# pcb_transformer_test.net
KiCad netlist of a schematic drawn in EAGLE
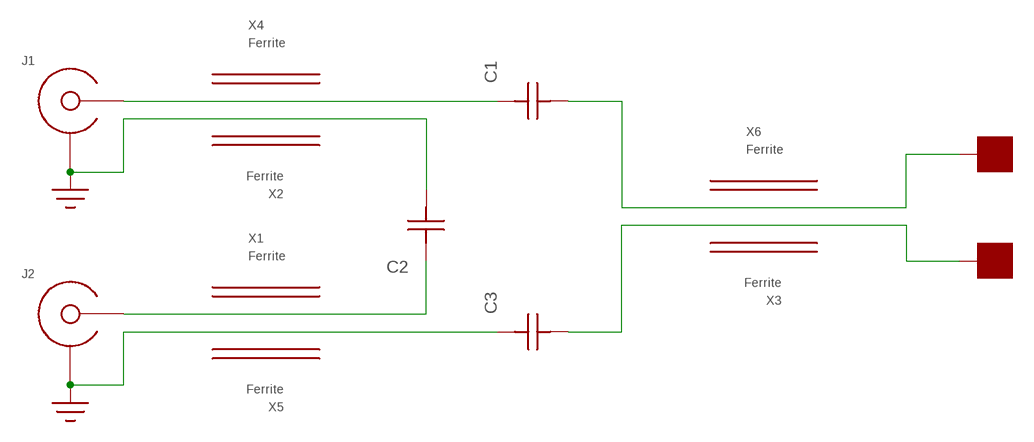
[diagram p0: schematic, sheet 1]

(export (version "E")
  (design (tool "Eeschema 10.0.6"))
  (components
    (comp (ref "C1")
      (value "C0603")
      (footprint "eagle-import:C0603")
      (libsource (lib "eagle-import") (part "C0603"))
    )
    (comp (ref "C2")
      (value "C0603")
      (footprint "eagle-import:C0603")
      (libsource (lib "eagle-import") (part "C0603"))
    )
    (comp (ref "C3")
      (value "C0603")
      (footprint "eagle-import:C0603")
      (libsource (lib "eagle-import") (part "C0603"))
    )
    (comp (ref "J1")
      (value "EDGE_LAUNCH_JACK")
      (footprint "eagle-import:EDGE_LAUNCH_RF_CON")
      (libsource (lib "eagle-import") (part "EDGE_LAUNCH_JACK"))
    )
    (comp (ref "J2")
      (value "EDGE_LAUNCH_JACK")
      (footprint "eagle-import:EDGE_LAUNCH_RF_CON")
      (libsource (lib "eagle-import") (part "EDGE_LAUNCH_JACK"))
    )
    (comp (ref "U$2")
      (value "PAD50MIL")
      (footprint "eagle-import:PAD_50MIL")
      (libsource (lib "eagle-import") (part "PAD50MIL"))
    )
    (comp (ref "U$5")
      (value "PAD50MIL")
      (footprint "eagle-import:PAD_50MIL")
      (libsource (lib "eagle-import") (part "PAD50MIL"))
    )
    (comp (ref "X1")
      (value "Ferrite")
      (footprint "eagle-import:FERRITE-MP0350")
      (libsource (lib "eagle-import") (part "FERRITE_PLATE"))
    )
    (comp (ref "X2")
      (value "Ferrite")
      (footprint "eagle-import:FERRITE-MP0350")
      (libsource (lib "eagle-import") (part "FERRITE_PLATE"))
    )
    (comp (ref "X3")
      (value "Ferrite")
      (footprint "eagle-import:FERRITE-MP0350")
      (libsource (lib "eagle-import") (part "FERRITE_PLATE"))
    )
    (comp (ref "X4")
      (value "Ferrite")
      (footprint "eagle-import:FERRITE-MP0350")
      (libsource (lib "eagle-import") (part "FERRITE_PLATE"))
    )
    (comp (ref "X5")
      (value "Ferrite")
      (footprint "eagle-import:FERRITE-MP0350")
      (libsource (lib "eagle-import") (part "FERRITE_PLATE"))
    )
    (comp (ref "X6")
      (value "Ferrite")
      (footprint "eagle-import:FERRITE-MP0350")
      (libsource (lib "eagle-import") (part "FERRITE_PLATE"))
    )
  )
  (nets
    (net (code "1") (name "GND") (class "Default")
      (node (ref "C2") (pin "P$1") (pinfunction "P$1_P$1") (pintype "bidirectional"))
      (node (ref "C3") (pin "P$2") (pinfunction "P$2_P$2") (pintype "bidirectional"))
      (node (ref "J1") (pin "GND@1") (pinfunction "SHIELD_GND@1") (pintype "bidirectional"))
      (node (ref "J1") (pin "GND@10") (pinfunction "SHIELD_GND@10") (pintype "bidirectional"))
      (node (ref "J1") (pin "GND@11") (pinfunction "SHIELD_GND@11") (pintype "bidirectional"))
      (node (ref "J1") (pin "GND@12") (pinfunction "SHIELD_GND@12") (pintype "bidirectional"))
      (node (ref "J1") (pin "GND@2") (pinfunction "SHIELD_GND@2") (pintype "bidirectional"))
      (node (ref "J1") (pin "GND@3") (pinfunction "SHIELD_GND@3") (pintype "bidirectional"))
      (node (ref "J1") (pin "GND@4") (pinfunction "SHIELD_GND@4") (pintype "bidirectional"))
      (node (ref "J1") (pin "GND@5") (pinfunction "SHIELD_GND@5") (pintype "bidirectional"))
      (node (ref "J1") (pin "GND@6") (pinfunction "SHIELD_GND@6") (pintype "bidirectional"))
      (node (ref "J1") (pin "GND@7") (pinfunction "SHIELD_GND@7") (pintype "bidirectional"))
      (node (ref "J1") (pin "GND@8") (pinfunction "SHIELD_GND@8") (pintype "bidirectional"))
      (node (ref "J1") (pin "GND@9") (pinfunction "SHIELD_GND@9") (pintype "bidirectional"))
      (node (ref "J1") (pin "SHIELD@1") (pinfunction "SHIELD_SHIELD@1") (pintype "bidirectional"))
      (node (ref "J1") (pin "SHIELD@2") (pinfunction "SHIELD_SHIELD@2") (pintype "bidirectional"))
      (node (ref "J2") (pin "GND@1") (pinfunction "SHIELD_GND@1") (pintype "bidirectional"))
      (node (ref "J2") (pin "GND@10") (pinfunction "SHIELD_GND@10") (pintype "bidirectional"))
      (node (ref "J2") (pin "GND@11") (pinfunction "SHIELD_GND@11") (pintype "bidirectional"))
      (node (ref "J2") (pin "GND@12") (pinfunction "SHIELD_GND@12") (pintype "bidirectional"))
      (node (ref "J2") (pin "GND@2") (pinfunction "SHIELD_GND@2") (pintype "bidirectional"))
      (node (ref "J2") (pin "GND@3") (pinfunction "SHIELD_GND@3") (pintype "bidirectional"))
      (node (ref "J2") (pin "GND@4") (pinfunction "SHIELD_GND@4") (pintype "bidirectional"))
      (node (ref "J2") (pin "GND@5") (pinfunction "SHIELD_GND@5") (pintype "bidirectional"))
      (node (ref "J2") (pin "GND@6") (pinfunction "SHIELD_GND@6") (pintype "bidirectional"))
      (node (ref "J2") (pin "GND@7") (pinfunction "SHIELD_GND@7") (pintype "bidirectional"))
      (node (ref "J2") (pin "GND@8") (pinfunction "SHIELD_GND@8") (pintype "bidirectional"))
      (node (ref "J2") (pin "GND@9") (pinfunction "SHIELD_GND@9") (pintype "bidirectional"))
      (node (ref "J2") (pin "SHIELD@1") (pinfunction "SHIELD_SHIELD@1") (pintype "bidirectional"))
      (node (ref "J2") (pin "SHIELD@2") (pinfunction "SHIELD_SHIELD@2") (pintype "bidirectional"))
    )
    (net (code "2") (name "Net-(C1-PadP$1)") (class "Default")
      (node (ref "C1") (pin "P$1") (pinfunction "P$1_P$1") (pintype "bidirectional"))
      (node (ref "U$2") (pin "P$1") (pinfunction "P$1_P$1") (pintype "bidirectional"))
    )
    (net (code "3") (name "Net-(C1-PadP$2)") (class "Default")
      (node (ref "C1") (pin "P$2") (pinfunction "P$2_P$2") (pintype "bidirectional"))
      (node (ref "J1") (pin "CENTER") (pinfunction "CENTER_CENTER") (pintype "bidirectional"))
    )
    (net (code "4") (name "Net-(C2-PadP$2)") (class "Default")
      (node (ref "C2") (pin "P$2") (pinfunction "P$2_P$2") (pintype "bidirectional"))
      (node (ref "J2") (pin "CENTER") (pinfunction "CENTER_CENTER") (pintype "bidirectional"))
    )
    (net (code "5") (name "Net-(C3-PadP$1)") (class "Default")
      (node (ref "C3") (pin "P$1") (pinfunction "P$1_P$1") (pintype "bidirectional"))
      (node (ref "U$5") (pin "P$1") (pinfunction "P$1_P$1") (pintype "bidirectional"))
    )
  )
)
